# NSTTC.net
KiCad netlist of a schematic drawn in Altium Designer
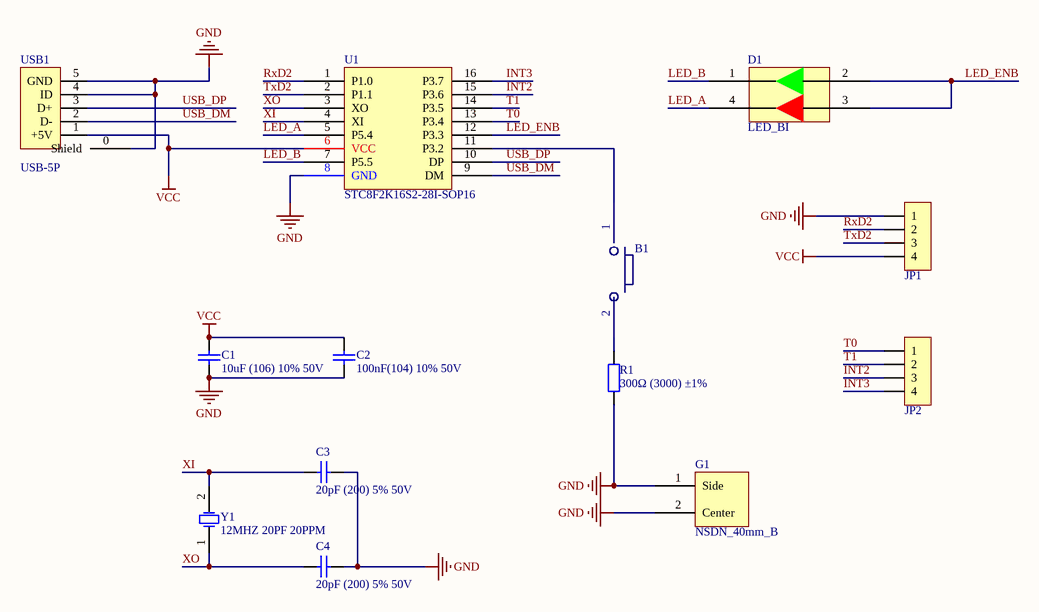
[diagram p0: NSTTC.SchDoc]

(export (version "E")
  (design (tool "Eeschema 10.0.6"))
  (components
    (comp (ref "B1")
      (value "USB_CTL")
      (footprint "MetalButton")
      (libsource (lib "MetalButton") (part "MetalButton"))
    )
    (comp (ref "C1")
      (value "10uF (106) 10% 50V")
      (footprint "1206_C")
      (description "贴片电容")
      (libsource (lib "Miscellaneous Devices LC") (part "1206 10uF (106) 10% 50V"))
    )
    (comp (ref "C2")
      (value "100nF(104) 10% 50V")
      (footprint "0805_C")
      (description "贴片电容")
      (libsource (lib "Miscellaneous Devices LC") (part "0805 100nF(104) 10% 50V"))
    )
    (comp (ref "C3")
      (value "20pF (200) 5% 50V")
      (footprint "0805_C")
      (description "贴片电容")
      (libsource (lib "Miscellaneous Devices LC") (part "0805 20pF (200) 5% 50V"))
    )
    (comp (ref "C4")
      (value "20pF (200) 5% 50V")
      (footprint "0805_C")
      (description "贴片电容")
      (libsource (lib "Miscellaneous Devices LC") (part "0805 20pF (200) 5% 50V"))
    )
    (comp (ref "D1") (value "LED_BI") (footprint "LED_BI") (libsource (lib "ngh-util") (part "LED_BI")))
    (comp (ref "G1")
      (value "NSDN_40mm_B")
      (footprint "NSDN_40mm_B")
      (libsource (lib "NSDN_40mm") (part "NSDN_40mm_B"))
    )
    (comp (ref "JP1")
      (value "HDR-1X4")
      (footprint "HDR2.54-WS-4P")
      (description "4P接插件")
      (fields (field (name "版权归属") "源创客"))
      (libsource (lib "4.5   - 接插件-脚距2.54") (part "Header 4"))
    )
    (comp (ref "JP2")
      (value "HDR-1X4")
      (footprint "HDR2.54-WS-4P")
      (description "4P接插件")
      (fields (field (name "版权归属") "源创客"))
      (libsource (lib "4.5   - 接插件-脚距2.54") (part "Header 4"))
    )
    (comp (ref "R1")
      (value "300Ω (3000) ±1%")
      (footprint "0805_R")
      (description "贴片电阻")
      (libsource (lib "Miscellaneous Devices LC") (part "0805 300Ω (3000) 1%"))
    )
    (comp (ref "U1")
      (value "STC8F2K16S2-28I-SOP16")
      (footprint "SOP16")
      (libsource (lib "Util") (part "STC8F2K16S2-28I-SOP16"))
    )
    (comp (ref "USB1")
      (value "USB-5P")
      (footprint "USB-MICRO_D")
      (description "微型USB母座")
      (fields (field (name "版权归属") "源创客"))
      (libsource (lib "4.1   - 接口类") (part "USB-5P"))
    )
    (comp (ref "Y1")
      (value "12MHZ 20PF 20PPM")
      (footprint "SMD-5032_2P")
      (description "贴片晶振")
      (libsource (lib "Miscellaneous Devices LC") (part "SMD-5032_2P 11.0592MHZ 20PF 20PPM"))
    )
  )
  (nets
    (net (code "1") (name "/INT2") (class "Default")
      (node (ref "JP2") (pin "3") (pinfunction "3_3") (pintype "passive"))
      (node (ref "U1") (pin "15") (pinfunction "P3.6_15") (pintype "passive"))
    )
    (net (code "2") (name "/INT3") (class "Default")
      (node (ref "JP2") (pin "4") (pinfunction "4_4") (pintype "passive"))
      (node (ref "U1") (pin "16") (pinfunction "P3.7_16") (pintype "passive"))
    )
    (net (code "3") (name "/LED_A") (class "Default")
      (node (ref "D1") (pin "4") (pinfunction "4_4") (pintype "passive"))
      (node (ref "U1") (pin "5") (pinfunction "P5.4_5") (pintype "passive"))
    )
    (net (code "4") (name "/LED_B") (class "Default")
      (node (ref "D1") (pin "1") (pinfunction "1_1") (pintype "passive"))
      (node (ref "U1") (pin "7") (pinfunction "P5.5_7") (pintype "passive"))
    )
    (net (code "5") (name "/LED_ENB") (class "Default")
      (node (ref "D1") (pin "2") (pinfunction "2_2") (pintype "passive"))
      (node (ref "D1") (pin "3") (pinfunction "3_3") (pintype "passive"))
      (node (ref "U1") (pin "12") (pinfunction "P3.3_12") (pintype "passive"))
    )
    (net (code "6") (name "/RxD2") (class "Default")
      (node (ref "JP1") (pin "2") (pinfunction "2_2") (pintype "passive"))
      (node (ref "U1") (pin "1") (pinfunction "P1.0_1") (pintype "passive"))
    )
    (net (code "7") (name "/T0") (class "Default")
      (node (ref "JP2") (pin "1") (pinfunction "1_1") (pintype "passive"))
      (node (ref "U1") (pin "13") (pinfunction "P3.4_13") (pintype "passive"))
    )
    (net (code "8") (name "/T1") (class "Default")
      (node (ref "JP2") (pin "2") (pinfunction "2_2") (pintype "passive"))
      (node (ref "U1") (pin "14") (pinfunction "P3.5_14") (pintype "passive"))
    )
    (net (code "9") (name "/TxD2") (class "Default")
      (node (ref "JP1") (pin "3") (pinfunction "3_3") (pintype "passive"))
      (node (ref "U1") (pin "2") (pinfunction "P1.1_2") (pintype "passive"))
    )
    (net (code "10") (name "/USB_DM") (class "Default")
      (node (ref "U1") (pin "9") (pinfunction "DM_9") (pintype "passive"))
      (node (ref "USB1") (pin "2") (pinfunction "D-_2") (pintype "passive"))
    )
    (net (code "11") (name "/USB_DP") (class "Default")
      (node (ref "U1") (pin "10") (pinfunction "DP_10") (pintype "passive"))
      (node (ref "USB1") (pin "3") (pinfunction "D+_3") (pintype "passive"))
    )
    (net (code "12") (name "/XI") (class "Default")
      (node (ref "C3") (pin "1") (pinfunction "1_1") (pintype "passive"))
      (node (ref "U1") (pin "4") (pinfunction "XI_4") (pintype "passive"))
      (node (ref "Y1") (pin "2") (pinfunction "OSC2_2") (pintype "passive"))
    )
    (net (code "13") (name "/XO") (class "Default")
      (node (ref "C4") (pin "2") (pinfunction "2_2") (pintype "passive"))
      (node (ref "U1") (pin "3") (pinfunction "XO_3") (pintype "passive"))
      (node (ref "Y1") (pin "1") (pinfunction "OSC1_1") (pintype "passive"))
    )
    (net (code "14") (name "GND") (class "Default")
      (node (ref "C1") (pin "2") (pinfunction "2_2") (pintype "passive"))
      (node (ref "C2") (pin "2") (pinfunction "2_2") (pintype "passive"))
      (node (ref "C3") (pin "2") (pinfunction "2_2") (pintype "passive"))
      (node (ref "C4") (pin "1") (pinfunction "1_1") (pintype "passive"))
      (node (ref "G1") (pin "1") (pinfunction "Side_1") (pintype "passive"))
      (node (ref "G1") (pin "2") (pinfunction "Center_2") (pintype "passive"))
      (node (ref "JP1") (pin "1") (pinfunction "1_1") (pintype "passive"))
      (node (ref "R1") (pin "1") (pinfunction "1_1") (pintype "passive"))
      (node (ref "U1") (pin "8") (pinfunction "GND_8") (pintype "passive"))
      (node (ref "USB1") (pin "0") (pinfunction "Shield_0") (pintype "passive"))
      (node (ref "USB1") (pin "4") (pinfunction "ID_4") (pintype "passive"))
      (node (ref "USB1") (pin "5") (pinfunction "GND_5") (pintype "passive"))
    )
    (net (code "15") (name "Net-(B1-Pad2)") (class "Default")
      (node (ref "B1") (pin "2") (pinfunction "2_2") (pintype "passive"))
      (node (ref "R1") (pin "2") (pinfunction "2_2") (pintype "passive"))
    )
    (net (code "16") (name "Net-(U1-P3.2)") (class "Default")
      (node (ref "B1") (pin "1") (pinfunction "1_1") (pintype "passive"))
      (node (ref "U1") (pin "11") (pinfunction "P3.2_11") (pintype "passive"))
    )
    (net (code "17") (name "VCC") (class "Default")
      (node (ref "C1") (pin "1") (pinfunction "1_1") (pintype "passive"))
      (node (ref "C2") (pin "1") (pinfunction "1_1") (pintype "passive"))
      (node (ref "JP1") (pin "4") (pinfunction "4_4") (pintype "passive"))
      (node (ref "U1") (pin "6") (pinfunction "VCC_6") (pintype "passive"))
      (node (ref "USB1") (pin "1") (pinfunction "+5V_1") (pintype "passive"))
    )
  )
)
